# timer_remote.net
KiCad netlist of a schematic drawn in EAGLE
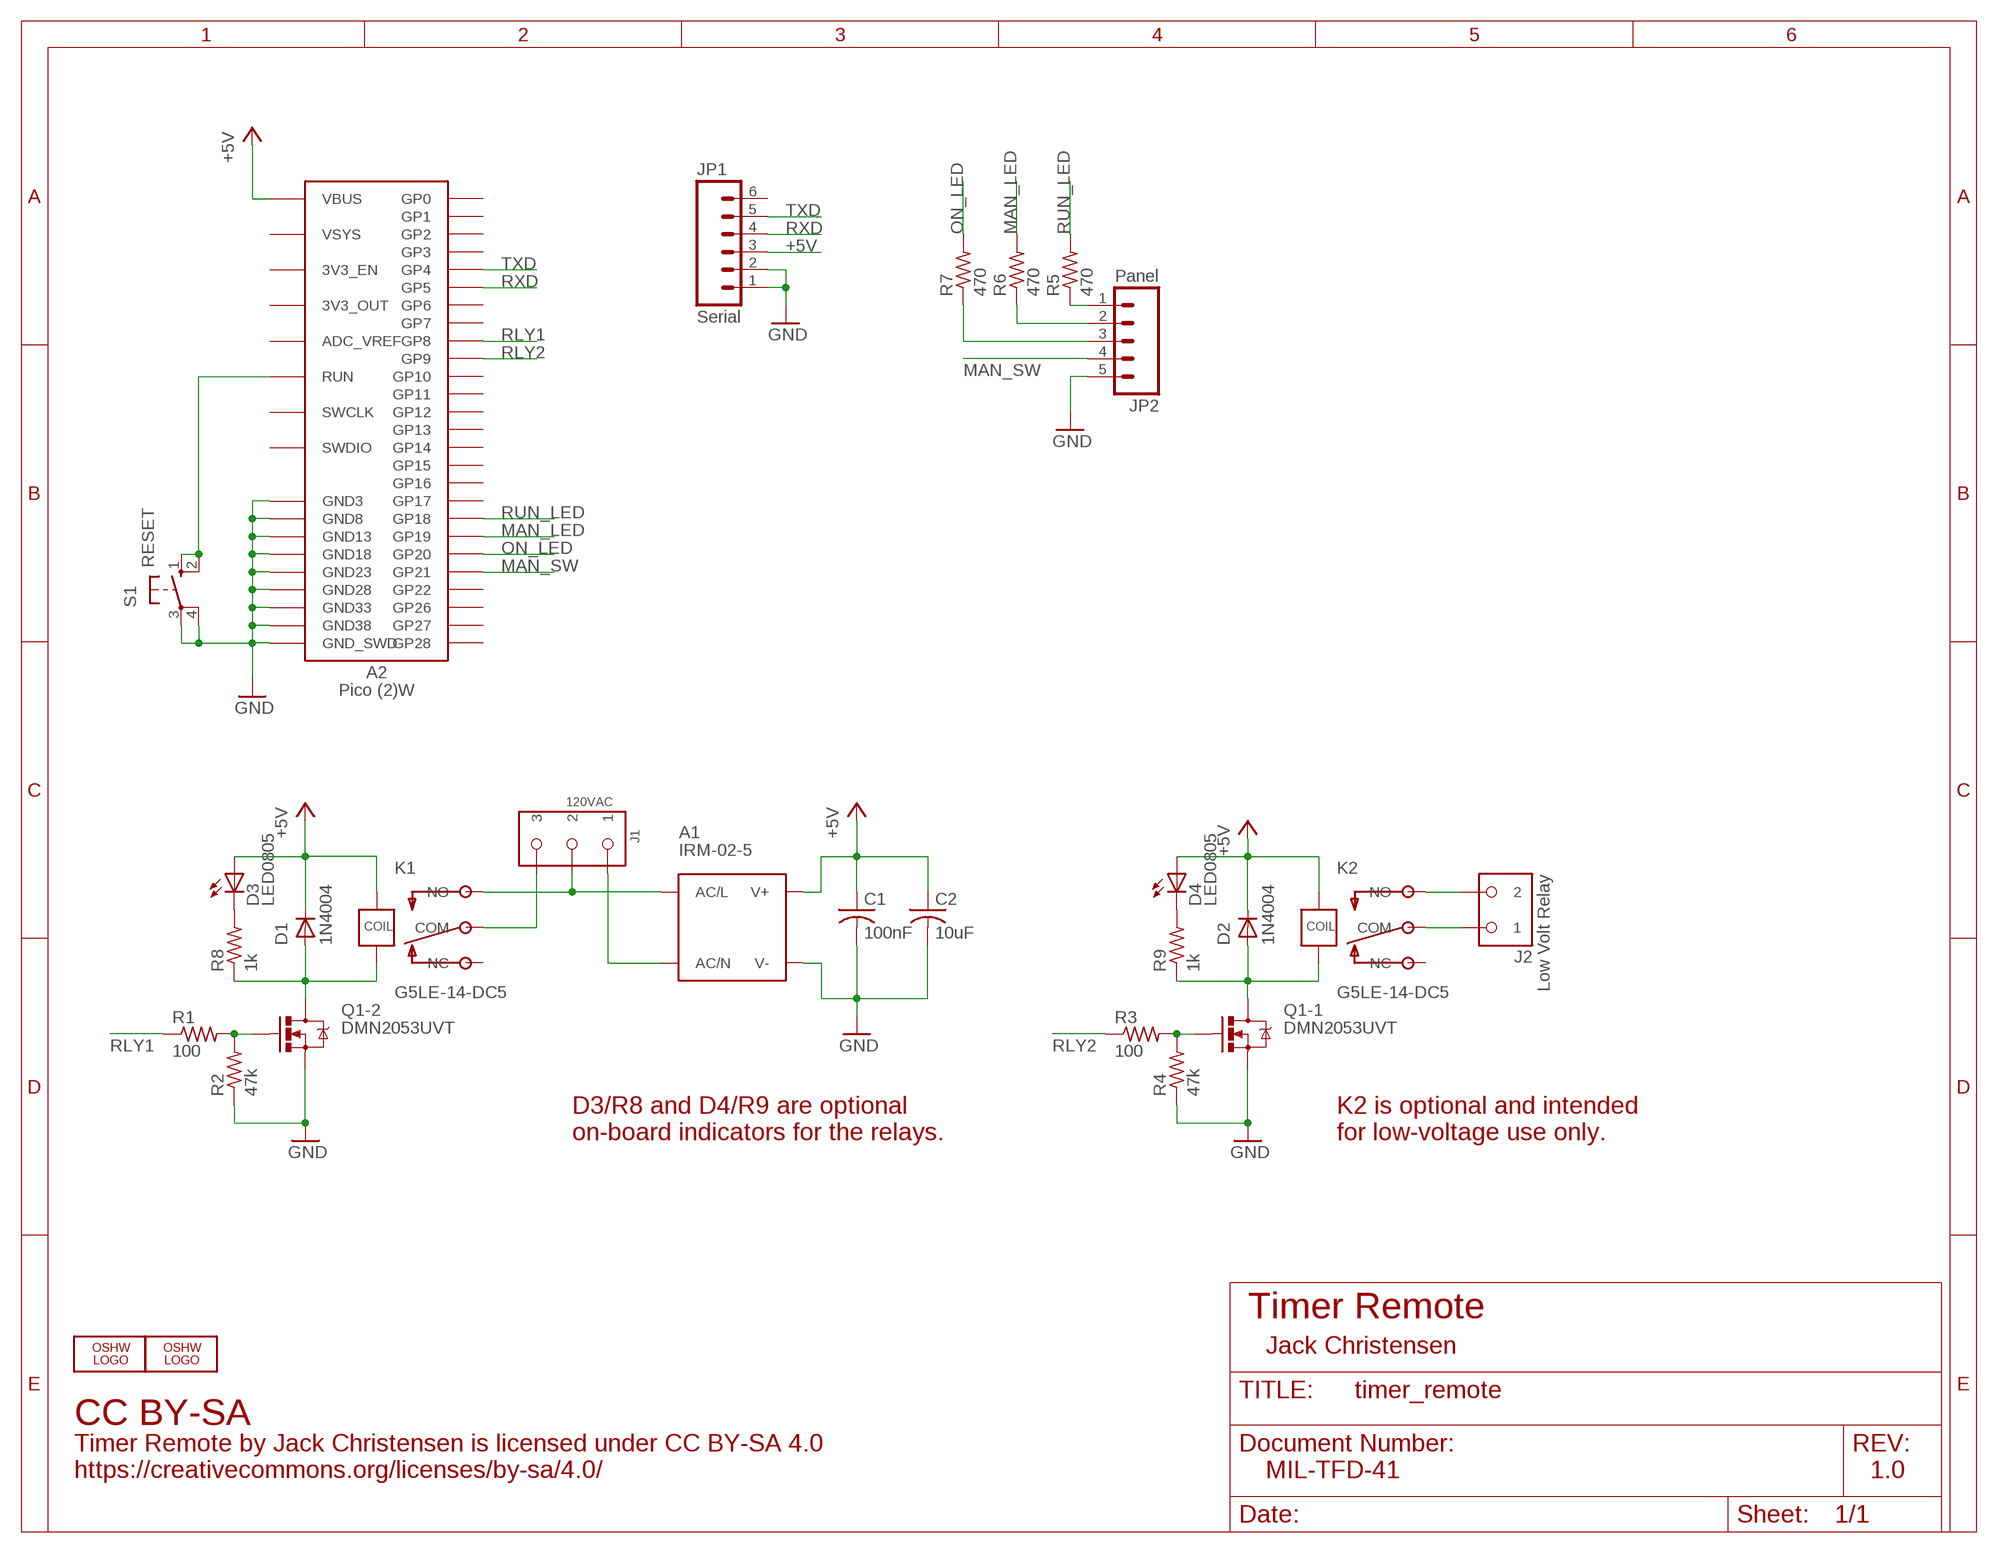
[diagram p0: schematic, sheet 1]

(export (version "E")
  (design (tool "Eeschema 10.0.6"))
  (components
    (comp (ref "A1")
      (value "IRM-02-5")
      (footprint "eagle-import:IRM-01")
      (libsource (lib "eagle-import") (part "IRM-01"))
    )
    (comp (ref "A2")
      (value "Pico (2)W")
      (footprint "eagle-import:PICO")
      (libsource (lib "eagle-import") (part "PICOPICO"))
    )
    (comp (ref "C1")
      (value "100nF")
      (footprint "eagle-import:M0805")
      (libsource (lib "eagle-import") (part "C-USM0805"))
    )
    (comp (ref "C2")
      (value "10uF")
      (footprint "eagle-import:M0805")
      (libsource (lib "eagle-import") (part "C-USM0805"))
    )
    (comp (ref "D1")
      (value "1N4004")
      (footprint "eagle-import:1N400X")
      (libsource (lib "eagle-import") (part "DIODE1N400X"))
    )
    (comp (ref "D2")
      (value "1N4004")
      (footprint "eagle-import:1N400X")
      (libsource (lib "eagle-import") (part "DIODE1N400X"))
    )
    (comp (ref "D3")
      (value "LED0805")
      (footprint "eagle-import:D0805A")
      (libsource (lib "eagle-import") (part "LEDD0805A"))
    )
    (comp (ref "D4")
      (value "LED0805")
      (footprint "eagle-import:D0805")
      (libsource (lib "eagle-import") (part "LEDD0805"))
    )
    (comp (ref "J1")
      (value "120VAC")
      (footprint "eagle-import:OST-TB-3-0.20")
      (libsource (lib "eagle-import") (part "OST-TB-35.08MM"))
    )
    (comp (ref "J2")
      (value "Low Volt Relay")
      (footprint "eagle-import:OST-TB-2-0.20")
      (libsource (lib "eagle-import") (part "OST-TB-20.20IN"))
    )
    (comp (ref "JP1")
      (value "Serial")
      (footprint "eagle-import:1X06_LOCK")
      (libsource (lib "eagle-import") (part "M06LOCK"))
    )
    (comp (ref "JP2")
      (value "Panel")
      (footprint "eagle-import:1X05_LOCK")
      (libsource (lib "eagle-import") (part "M05LOCK"))
    )
    (comp (ref "K1")
      (value "G5LE-14-DC5")
      (footprint "eagle-import:NAIS-JS1-5V")
      (libsource (lib "eagle-import") (part "RELAY-SPDT"))
    )
    (comp (ref "K2")
      (value "G5LE-14-DC5")
      (footprint "eagle-import:NAIS-JS1-5V")
      (libsource (lib "eagle-import") (part "RELAY-SPDT"))
    )
    (comp (ref "LOGO1")
      (value "OSHW_LOGO_10MILX0200-NT")
      (footprint "eagle-import:OSHW_10X200_NOTEXT")
      (libsource (lib "eagle-import") (part "OSHW_LOGO_10MILX0200-NT"))
    )
    (comp (ref "LOGO2")
      (value "OSHW_LOGO_10MILX0200-NT")
      (footprint "eagle-import:OSHW_10X200_NOTEXT")
      (libsource (lib "eagle-import") (part "OSHW_LOGO_10MILX0200-NT"))
    )
    (comp (ref "Q1")
      (value "DMN2053UVT")
      (footprint "eagle-import:SOT23-6")
      (libsource (lib "eagle-import") (part "DUAL-MOSFETSOT23-6"))
    )
    (comp (ref "R1")
      (value "100")
      (footprint "eagle-import:M0805")
      (libsource (lib "eagle-import") (part "R-US_M0805"))
    )
    (comp (ref "R2")
      (value "47k")
      (footprint "eagle-import:M0805")
      (libsource (lib "eagle-import") (part "R-US_M0805"))
    )
    (comp (ref "R3")
      (value "100")
      (footprint "eagle-import:M0805")
      (libsource (lib "eagle-import") (part "R-US_M0805"))
    )
    (comp (ref "R4")
      (value "47k")
      (footprint "eagle-import:M0805")
      (libsource (lib "eagle-import") (part "R-US_M0805"))
    )
    (comp (ref "R5")
      (value "470")
      (footprint "eagle-import:M0805")
      (libsource (lib "eagle-import") (part "R-US_M0805"))
    )
    (comp (ref "R6")
      (value "470")
      (footprint "eagle-import:M0805")
      (libsource (lib "eagle-import") (part "R-US_M0805"))
    )
    (comp (ref "R7")
      (value "470")
      (footprint "eagle-import:M0805")
      (libsource (lib "eagle-import") (part "R-US_M0805"))
    )
    (comp (ref "R8")
      (value "1k")
      (footprint "eagle-import:M0805")
      (libsource (lib "eagle-import") (part "R-US_M0805"))
    )
    (comp (ref "R9")
      (value "1k")
      (footprint "eagle-import:M0805")
      (libsource (lib "eagle-import") (part "R-US_M0805"))
    )
    (comp (ref "S1")
      (value "RESET")
      (footprint "eagle-import:B3F-10XXOCT")
      (libsource (lib "eagle-import") (part "10-XXOCT"))
    )
  )
  (nets
    (net (code "1") (name "+5V") (class "Default")
      (node (ref "A1") (pin "V+") (pinfunction "V+_V+") (pintype "bidirectional"))
      (node (ref "A2") (pin "P$40") (pinfunction "VBUS_P$40") (pintype "bidirectional"))
      (node (ref "C1") (pin "1") (pinfunction "1_1") (pintype "passive"))
      (node (ref "C2") (pin "1") (pinfunction "1_1") (pintype "passive"))
      (node (ref "D1") (pin "K") (pinfunction "K_K") (pintype "passive"))
      (node (ref "D2") (pin "K") (pinfunction "K_K") (pintype "passive"))
      (node (ref "D3") (pin "A") (pinfunction "A_A") (pintype "passive"))
      (node (ref "D4") (pin "A") (pinfunction "A_A") (pintype "passive"))
      (node (ref "JP1") (pin "3") (pinfunction "3_3") (pintype "passive"))
      (node (ref "K1") (pin "C1") (pinfunction "C1_C1") (pintype "passive"))
      (node (ref "K2") (pin "C1") (pinfunction "C1_C1") (pintype "passive"))
    )
    (net (code "2") (name "/MAN_LED") (class "Default")
      (node (ref "A2") (pin "P$25") (pinfunction "GP19_P$25") (pintype "bidirectional"))
      (node (ref "R6") (pin "2") (pinfunction "2_2") (pintype "passive"))
    )
    (net (code "3") (name "/MAN_SW") (class "Default")
      (node (ref "A2") (pin "P$27") (pinfunction "GP21_P$27") (pintype "bidirectional"))
      (node (ref "JP2") (pin "4") (pinfunction "4_4") (pintype "passive"))
    )
    (net (code "4") (name "/ON_LED") (class "Default")
      (node (ref "A2") (pin "P$26") (pinfunction "GP20_P$26") (pintype "bidirectional"))
      (node (ref "R7") (pin "2") (pinfunction "2_2") (pintype "passive"))
    )
    (net (code "5") (name "/RLY1") (class "Default")
      (node (ref "A2") (pin "P$11") (pinfunction "GP8_P$11") (pintype "bidirectional"))
      (node (ref "R1") (pin "1") (pinfunction "1_1") (pintype "passive"))
    )
    (net (code "6") (name "/RLY2") (class "Default")
      (node (ref "A2") (pin "P$12") (pinfunction "GP9_P$12") (pintype "bidirectional"))
      (node (ref "R3") (pin "1") (pinfunction "1_1") (pintype "passive"))
    )
    (net (code "7") (name "/RUN_LED") (class "Default")
      (node (ref "A2") (pin "P$24") (pinfunction "GP18_P$24") (pintype "bidirectional"))
      (node (ref "R5") (pin "2") (pinfunction "2_2") (pintype "passive"))
    )
    (net (code "8") (name "/RXD") (class "Default")
      (node (ref "A2") (pin "P$07") (pinfunction "GP5_P$07") (pintype "bidirectional"))
      (node (ref "JP1") (pin "4") (pinfunction "4_4") (pintype "passive"))
    )
    (net (code "9") (name "/TXD") (class "Default")
      (node (ref "A2") (pin "P$06") (pinfunction "GP4_P$06") (pintype "bidirectional"))
      (node (ref "JP1") (pin "5") (pinfunction "5_5") (pintype "passive"))
    )
    (net (code "10") (name "GND") (class "Default")
      (node (ref "A1") (pin "V-") (pinfunction "V-_V-") (pintype "bidirectional"))
      (node (ref "A2") (pin "P$03") (pinfunction "GND3_P$03") (pintype "bidirectional"))
      (node (ref "A2") (pin "P$08") (pinfunction "GND8_P$08") (pintype "bidirectional"))
      (node (ref "A2") (pin "P$13") (pinfunction "GND13_P$13") (pintype "bidirectional"))
      (node (ref "A2") (pin "P$18") (pinfunction "GND18_P$18") (pintype "bidirectional"))
      (node (ref "A2") (pin "P$23") (pinfunction "GND23_P$23") (pintype "bidirectional"))
      (node (ref "A2") (pin "P$28") (pinfunction "GND28_P$28") (pintype "bidirectional"))
      (node (ref "A2") (pin "P$33") (pinfunction "GND33_P$33") (pintype "bidirectional"))
      (node (ref "A2") (pin "P$38") (pinfunction "GND38_P$38") (pintype "bidirectional"))
      (node (ref "A2") (pin "P$SWGND") (pinfunction "GND_SWD_P$SWGND") (pintype "bidirectional"))
      (node (ref "C1") (pin "2") (pinfunction "2_2") (pintype "passive"))
      (node (ref "C2") (pin "2") (pinfunction "2_2") (pintype "passive"))
      (node (ref "JP1") (pin "1") (pinfunction "1_1") (pintype "passive"))
      (node (ref "JP1") (pin "2") (pinfunction "2_2") (pintype "passive"))
      (node (ref "JP2") (pin "5") (pinfunction "5_5") (pintype "passive"))
      (node (ref "Q1") (pin "2") (pinfunction "S_2") (pintype "passive"))
      (node (ref "Q1") (pin "5") (pinfunction "S_5") (pintype "passive"))
      (node (ref "R2") (pin "1") (pinfunction "1_1") (pintype "passive"))
      (node (ref "R4") (pin "1") (pinfunction "1_1") (pintype "passive"))
      (node (ref "S1") (pin "3") (pinfunction "P_3") (pintype "passive"))
      (node (ref "S1") (pin "4") (pinfunction "P1_4") (pintype "passive"))
    )
    (net (code "11") (name "Net-(A2-RUN)") (class "Default")
      (node (ref "A2") (pin "P$30") (pinfunction "RUN_P$30") (pintype "bidirectional"))
      (node (ref "S1") (pin "1") (pinfunction "S_1") (pintype "passive"))
      (node (ref "S1") (pin "2") (pinfunction "S1_2") (pintype "passive"))
    )
    (net (code "12") (name "Net-(D3-C)") (class "Default")
      (node (ref "D3") (pin "K") (pinfunction "C_K") (pintype "passive"))
      (node (ref "R8") (pin "2") (pinfunction "2_2") (pintype "passive"))
    )
    (net (code "13") (name "Net-(D4-C)") (class "Default")
      (node (ref "D4") (pin "K") (pinfunction "C_K") (pintype "passive"))
      (node (ref "R9") (pin "2") (pinfunction "2_2") (pintype "passive"))
    )
    (net (code "14") (name "Net-(J1-1)") (class "Default")
      (node (ref "A1") (pin "AC/N") (pinfunction "AC/N_AC/N") (pintype "bidirectional"))
      (node (ref "J1") (pin "P$1") (pinfunction "1_P$1") (pintype "passive"))
    )
    (net (code "15") (name "Net-(J1-2)") (class "Default")
      (node (ref "A1") (pin "AC/L") (pinfunction "AC/L_AC/L") (pintype "bidirectional"))
      (node (ref "J1") (pin "P$2") (pinfunction "2_P$2") (pintype "passive"))
      (node (ref "K1") (pin "NO") (pinfunction "NO_NO") (pintype "passive"))
    )
    (net (code "16") (name "Net-(J1-3)") (class "Default")
      (node (ref "J1") (pin "P$3") (pinfunction "3_P$3") (pintype "passive"))
      (node (ref "K1") (pin "COM") (pinfunction "COM_COM") (pintype "passive"))
    )
    (net (code "17") (name "Net-(J2-1)") (class "Default")
      (node (ref "J2") (pin "P$1") (pinfunction "1_P$1") (pintype "passive"))
      (node (ref "K2") (pin "COM") (pinfunction "COM_COM") (pintype "passive"))
    )
    (net (code "18") (name "Net-(J2-2)") (class "Default")
      (node (ref "J2") (pin "P$2") (pinfunction "2_P$2") (pintype "passive"))
      (node (ref "K2") (pin "NO") (pinfunction "NO_NO") (pintype "passive"))
    )
    (net (code "19") (name "Net-(JP2-Pad1)") (class "Default")
      (node (ref "JP2") (pin "1") (pinfunction "1_1") (pintype "passive"))
      (node (ref "R5") (pin "1") (pinfunction "1_1") (pintype "passive"))
    )
    (net (code "20") (name "Net-(JP2-Pad2)") (class "Default")
      (node (ref "JP2") (pin "2") (pinfunction "2_2") (pintype "passive"))
      (node (ref "R6") (pin "1") (pinfunction "1_1") (pintype "passive"))
    )
    (net (code "21") (name "Net-(JP2-Pad3)") (class "Default")
      (node (ref "JP2") (pin "3") (pinfunction "3_3") (pintype "passive"))
      (node (ref "R7") (pin "1") (pinfunction "1_1") (pintype "passive"))
    )
    (net (code "22") (name "Net-(Q1A-D)") (class "Default")
      (node (ref "D2") (pin "A") (pinfunction "A_A") (pintype "passive"))
      (node (ref "K2") (pin "C2") (pinfunction "C2_C2") (pintype "bidirectional"))
      (node (ref "Q1") (pin "6") (pinfunction "D_6") (pintype "passive"))
      (node (ref "R9") (pin "1") (pinfunction "1_1") (pintype "passive"))
    )
    (net (code "23") (name "Net-(Q1A-G)") (class "Default")
      (node (ref "Q1") (pin "1") (pinfunction "G_1") (pintype "passive"))
      (node (ref "R3") (pin "2") (pinfunction "2_2") (pintype "passive"))
      (node (ref "R4") (pin "2") (pinfunction "2_2") (pintype "passive"))
    )
    (net (code "24") (name "Net-(Q1B-D)") (class "Default")
      (node (ref "D1") (pin "A") (pinfunction "A_A") (pintype "passive"))
      (node (ref "K1") (pin "C2") (pinfunction "C2_C2") (pintype "bidirectional"))
      (node (ref "Q1") (pin "4") (pinfunction "D_4") (pintype "passive"))
      (node (ref "R8") (pin "1") (pinfunction "1_1") (pintype "passive"))
    )
    (net (code "25") (name "Net-(Q1B-G)") (class "Default")
      (node (ref "Q1") (pin "3") (pinfunction "G_3") (pintype "passive"))
      (node (ref "R1") (pin "2") (pinfunction "2_2") (pintype "passive"))
      (node (ref "R2") (pin "2") (pinfunction "2_2") (pintype "passive"))
    )
    (net (code "26") (name "unconnected-(A2-3V3_EN-PadP$37)") (class "Default")
      (node (ref "A2") (pin "P$37") (pinfunction "3V3_EN_P$37") (pintype "bidirectional"))
    )
    (net (code "27") (name "unconnected-(A2-3V3_OUT-PadP$36)") (class "Default")
      (node (ref "A2") (pin "P$36") (pinfunction "3V3_OUT_P$36") (pintype "bidirectional"))
    )
    (net (code "28") (name "unconnected-(A2-ADC_VREF-PadP$35)") (class "Default")
      (node (ref "A2") (pin "P$35") (pinfunction "ADC_VREF_P$35") (pintype "bidirectional"))
    )
    (net (code "29") (name "unconnected-(A2-GP0-PadP$01)") (class "Default")
      (node (ref "A2") (pin "P$01") (pinfunction "GP0_P$01") (pintype "bidirectional"))
    )
    (net (code "30") (name "unconnected-(A2-GP1-PadP$02)") (class "Default")
      (node (ref "A2") (pin "P$02") (pinfunction "GP1_P$02") (pintype "bidirectional"))
    )
    (net (code "31") (name "unconnected-(A2-GP2-PadP$04)") (class "Default")
      (node (ref "A2") (pin "P$04") (pinfunction "GP2_P$04") (pintype "bidirectional"))
    )
    (net (code "32") (name "unconnected-(A2-GP3-PadP$05)") (class "Default")
      (node (ref "A2") (pin "P$05") (pinfunction "GP3_P$05") (pintype "bidirectional"))
    )
    (net (code "33") (name "unconnected-(A2-GP6-PadP$09)") (class "Default")
      (node (ref "A2") (pin "P$09") (pinfunction "GP6_P$09") (pintype "bidirectional"))
    )
    (net (code "34") (name "unconnected-(A2-GP7-PadP$10)") (class "Default")
      (node (ref "A2") (pin "P$10") (pinfunction "GP7_P$10") (pintype "bidirectional"))
    )
    (net (code "35") (name "unconnected-(A2-GP10-PadP$14)") (class "Default")
      (node (ref "A2") (pin "P$14") (pinfunction "GP10_P$14") (pintype "bidirectional"))
    )
    (net (code "36") (name "unconnected-(A2-GP11-PadP$15)") (class "Default")
      (node (ref "A2") (pin "P$15") (pinfunction "GP11_P$15") (pintype "bidirectional"))
    )
    (net (code "37") (name "unconnected-(A2-GP12-PadP$16)") (class "Default")
      (node (ref "A2") (pin "P$16") (pinfunction "GP12_P$16") (pintype "bidirectional"))
    )
    (net (code "38") (name "unconnected-(A2-GP13-PadP$17)") (class "Default")
      (node (ref "A2") (pin "P$17") (pinfunction "GP13_P$17") (pintype "bidirectional"))
    )
    (net (code "39") (name "unconnected-(A2-GP14-PadP$19)") (class "Default")
      (node (ref "A2") (pin "P$19") (pinfunction "GP14_P$19") (pintype "bidirectional"))
    )
    (net (code "40") (name "unconnected-(A2-GP15-PadP$20)") (class "Default")
      (node (ref "A2") (pin "P$20") (pinfunction "GP15_P$20") (pintype "bidirectional"))
    )
    (net (code "41") (name "unconnected-(A2-GP16-PadP$21)") (class "Default")
      (node (ref "A2") (pin "P$21") (pinfunction "GP16_P$21") (pintype "bidirectional"))
    )
    (net (code "42") (name "unconnected-(A2-GP17-PadP$22)") (class "Default")
      (node (ref "A2") (pin "P$22") (pinfunction "GP17_P$22") (pintype "bidirectional"))
    )
    (net (code "43") (name "unconnected-(A2-GP22-PadP$29)") (class "Default")
      (node (ref "A2") (pin "P$29") (pinfunction "GP22_P$29") (pintype "bidirectional"))
    )
    (net (code "44") (name "unconnected-(A2-GP26-PadP$31)") (class "Default")
      (node (ref "A2") (pin "P$31") (pinfunction "GP26_P$31") (pintype "bidirectional"))
    )
    (net (code "45") (name "unconnected-(A2-GP27-PadP$32)") (class "Default")
      (node (ref "A2") (pin "P$32") (pinfunction "GP27_P$32") (pintype "bidirectional"))
    )
    (net (code "46") (name "unconnected-(A2-GP28-PadP$34)") (class "Default")
      (node (ref "A2") (pin "P$34") (pinfunction "GP28_P$34") (pintype "bidirectional"))
    )
    (net (code "47") (name "unconnected-(A2-SWCLK-PadP$SWCLK)") (class "Default")
      (node (ref "A2") (pin "P$SWCLK") (pinfunction "SWCLK_P$SWCLK") (pintype "bidirectional"))
    )
    (net (code "48") (name "unconnected-(A2-SWDIO-PadP$SWDIO)") (class "Default")
      (node (ref "A2") (pin "P$SWDIO") (pinfunction "SWDIO_P$SWDIO") (pintype "bidirectional"))
    )
    (net (code "49") (name "unconnected-(A2-VSYS-PadP$39)") (class "Default")
      (node (ref "A2") (pin "P$39") (pinfunction "VSYS_P$39") (pintype "bidirectional"))
    )
    (net (code "50") (name "unconnected-(JP1-Pad6)") (class "Default")
      (node (ref "JP1") (pin "6") (pinfunction "6_6") (pintype "passive"))
    )
    (net (code "51") (name "unconnected-(K1-PadNC)") (class "Default")
      (node (ref "K1") (pin "NC") (pinfunction "NC_NC") (pintype "passive"))
    )
    (net (code "52") (name "unconnected-(K2-PadNC)") (class "Default")
      (node (ref "K2") (pin "NC") (pinfunction "NC_NC") (pintype "passive"))
    )
  )
)
